# power_supply.net
KiCad netlist of a schematic drawn in Altium Designer
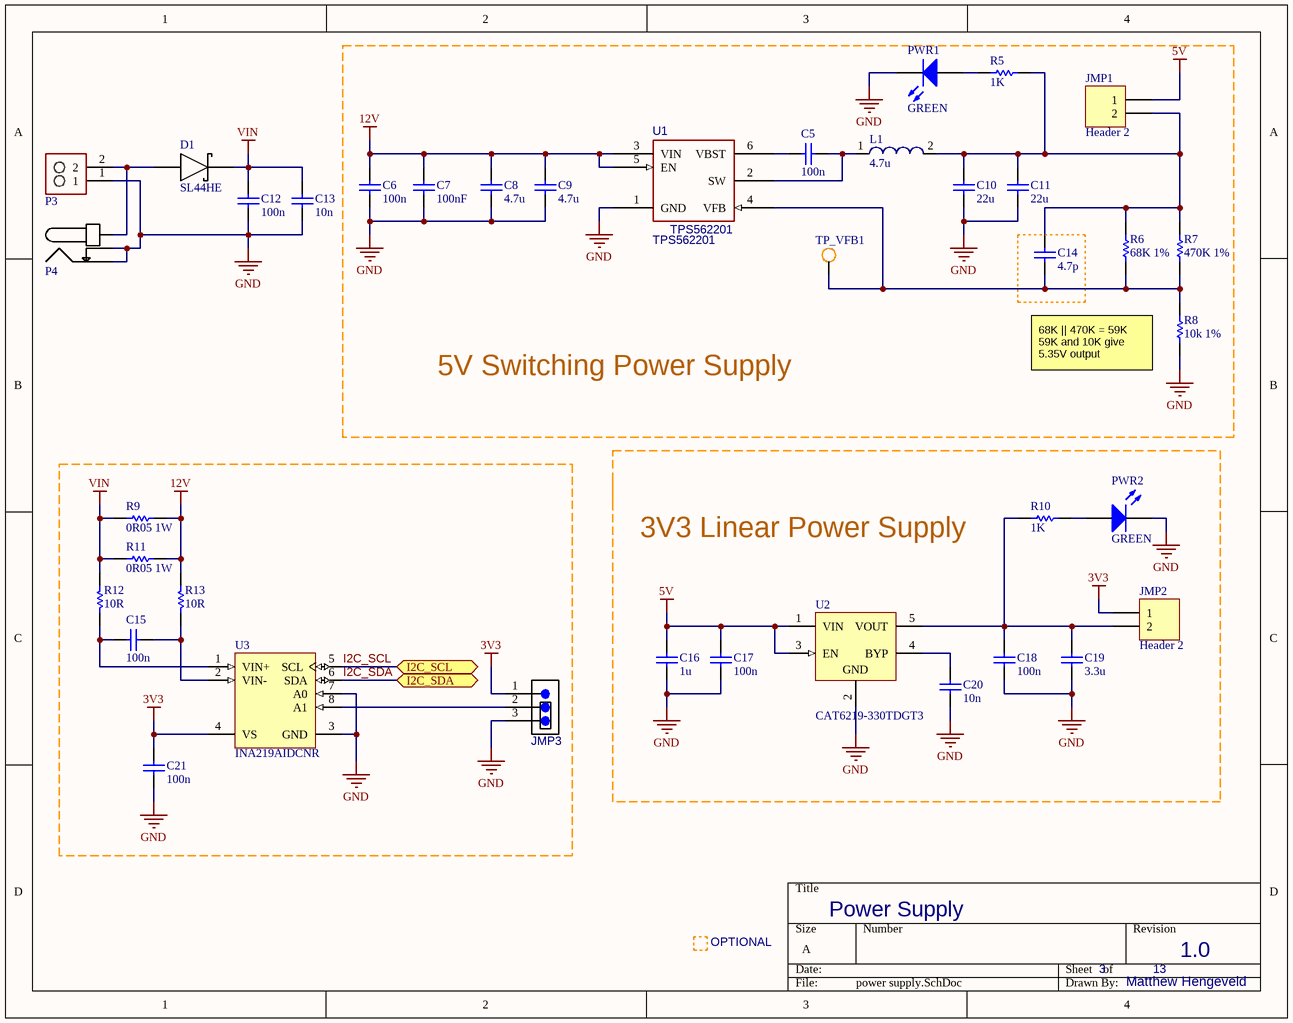
[diagram p0: power supply.SchDoc]

(export (version "E")
  (design (tool "Eeschema 10.0.6"))
  (components
    (comp (ref "C5")
      (value "100n")
      (footprint "CAPC2113X100X50LL30T25")
      (fields (field (name "MANUFACTURER") "Kemet") (field (name "PART NUMBER") "C0805X104K5RACTU"))
      (libsource (lib "Altium Content Vault") (part "CAP"))
    )
    (comp (ref "C6")
      (value "100n")
      (footprint "CAPC1608X90X35LL15T15")
      (description "Chip Capacitor, 100 nF, +/- 10%, 50 V, -55 to 125 degC, 0603 (1608 Metric), RoHS, Tape and Reel")
      (fields (field (name "TOLERANCE") "10%"))
      (libsource (lib "Altium Content Vault") (part "CAP-NP-2"))
    )
    (comp (ref "C7")
      (value "100nF")
      (footprint "CAPC2013X94X50LL20T25")
      (fields
        (field (name "PART NUMBER") "08055C104K4T2A")
        (field (name "MANUFACTURER") "AVX Interconnect / Elco")
      )
      (libsource (lib "Altium Content Vault") (part "CAP"))
    )
    (comp (ref "C8")
      (value "4.7u")
      (footprint "CAPC3225X220X20ML40")
      (description "Chip Capacitor, 4.7 uF, +/- 20%, 100 V, -55 to 125 degC, 1210 (3225 Metric), RoHS, Tape and Reel")
      (fields
        (field (name "PCN PART NUMBER") "MLCCPartNumberChange30/Nov/2012")
        (field (name "MANUFACTURER") "TDK")
      )
      (libsource (lib "Altium Content Vault") (part "CAP-NP-2"))
    )
    (comp (ref "C9")
      (value "4.7u")
      (footprint "CAPC3225X220X20ML40")
      (description "Chip Capacitor, 4.7 uF, +/- 20%, 100 V, -55 to 125 degC, 1210 (3225 Metric), RoHS, Tape and Reel")
      (fields
        (field (name "PCN PART NUMBER") "MLCCPartNumberChange30/Nov/2012")
        (field (name "MANUFACTURER") "TDK")
      )
      (libsource (lib "Altium Content Vault") (part "CAP-NP-2"))
    )
    (comp (ref "C10")
      (value "22u")
      (footprint "CAPC3225X220X20ML40")
      (description "Chip Capacitor, 4.7 uF, +/- 20%, 100 V, -55 to 125 degC, 1210 (3225 Metric), RoHS, Tape and Reel")
      (fields
        (field (name "PCN PART NUMBER") "MLCCPartNumberChange30/Nov/2012")
        (field (name "MANUFACTURER") "TDK")
      )
      (libsource (lib "Altium Content Vault") (part "CAP-NP-2"))
    )
    (comp (ref "C11")
      (value "22u")
      (footprint "CAPC3225X220X20ML40")
      (description "Chip Capacitor, 4.7 uF, +/- 20%, 100 V, -55 to 125 degC, 1210 (3225 Metric), RoHS, Tape and Reel")
      (fields
        (field (name "PCN PART NUMBER") "MLCCPartNumberChange30/Nov/2012")
        (field (name "MANUFACTURER") "TDK")
      )
      (libsource (lib "Altium Content Vault") (part "CAP-NP-2"))
    )
    (comp (ref "C12")
      (value "100n")
      (footprint "CAPC2013X95X45LL15T25")
      (fields (field (name "PART NUMBER") "GCM2195C1H103JA16D") (field (name "MANUFACTURER") "Murata"))
      (libsource (lib "Altium Content Vault") (part "CAP"))
    )
    (comp (ref "C13")
      (value "10n")
      (footprint "CAPC2013X95X45LL15T25")
      (fields (field (name "PART NUMBER") "GCM2195C1H103JA16D") (field (name "MANUFACTURER") "Murata"))
      (libsource (lib "Altium Content Vault") (part "CAP"))
    )
    (comp (ref "C14")
      (value "4.7p")
      (footprint "CAPC1608X87X35LL15T15")
      (fields (field (name "MANUFACTURER") "Kemet") (field (name "PART NUMBER") "C0603C104K3RACTU"))
      (libsource (lib "Altium Content Vault") (part "CAP"))
    )
    (comp (ref "C15")
      (value "100n")
      (footprint "CAPC1608X87X35LL15T15")
      (fields (field (name "PART NUMBER") "C0603X104K5RACTU") (field (name "MANUFACTURER") "Kemet"))
      (libsource (lib "Altium Content Vault") (part "CAP"))
    )
    (comp (ref "C16")
      (value "1u")
      (footprint "CAPC2013X140X50LL20T25")
      (fields
        (field (name "PART NUMBER") "0805ZC105KAT2A")
        (field (name "MANUFACTURER") "AVX Interconnect / Elco")
      )
      (libsource (lib "Altium Content Vault") (part "CAP"))
    )
    (comp (ref "C17")
      (value "100n")
      (footprint "CAPC1608X87X35LL15T15")
      (fields (field (name "MANUFACTURER") "Kemet") (field (name "PART NUMBER") "C0603C104K3RACTU"))
      (libsource (lib "Altium Content Vault") (part "CAP"))
    )
    (comp (ref "C18")
      (value "100n")
      (footprint "CAPC1608X87X35LL15T15")
      (fields (field (name "MANUFACTURER") "Kemet") (field (name "PART NUMBER") "C0603C104K3RACTU"))
      (libsource (lib "Altium Content Vault") (part "CAP"))
    )
    (comp (ref "C19")
      (value "3.3u")
      (footprint "CAPC3225X220X20ML40")
      (description "Chip Capacitor, 4.7 uF, +/- 20%, 100 V, -55 to 125 degC, 1210 (3225 Metric), RoHS, Tape and Reel")
      (fields
        (field (name "PCN PART NUMBER") "MLCCPartNumberChange30/Nov/2012")
        (field (name "MANUFACTURER") "TDK")
      )
      (libsource (lib "Altium Content Vault") (part "CAP-NP-2"))
    )
    (comp (ref "C20")
      (value "10n")
      (footprint "CAPC1608X87X35LL15T15")
      (fields (field (name "MANUFACTURER") "Kemet") (field (name "PART NUMBER") "C0603C104K3RACTU"))
      (libsource (lib "Altium Content Vault") (part "CAP"))
    )
    (comp (ref "C21")
      (value "100n")
      (footprint "CAPC1608X87X35LL15T15")
      (fields (field (name "PART NUMBER") "C0603X104K5RACTU") (field (name "MANUFACTURER") "Kemet"))
      (libsource (lib "Altium Content Vault") (part "CAP"))
    )
    (comp (ref "D1")
      (value "SL44HE")
      (footprint "SMC Diode")
      (description "Schottky Power Rectifier, 2-Pin SMC, 40V, 8A")
      (fields (field (name "PARTNUMBER") "MBRS540T3") (field (name "MANUFACTURER") "On Semiconductor"))
      (libsource (lib "Hengeveld") (part "SL44HE"))
    )
    (comp (ref "JMP1")
      (value "Header 2")
      (footprint "HDR1X2")
      (description "Header, 2-Pin")
      (fields (field (name "PUBLISHER") "Altium Limited"))
      (libsource (lib "") (part "Header 2_1"))
    )
    (comp (ref "JMP2")
      (value "Header 2")
      (footprint "HDR1X2")
      (description "Header, 2-Pin")
      (fields (field (name "PUBLISHER") "Altium Limited"))
      (libsource (lib "Hengeveld") (part "Header 2"))
    )
    (comp (ref "JMP3")
      (value "SMD_JMP")
      (footprint "0603_JUMPER")
      (libsource (lib "Hengeveld") (part "SMD_JMP"))
    )
    (comp (ref "L1")
      (value "4.7u")
      (footprint "WE-LQS 6045")
      (description "WE-LQS SMD Power Inductor, L=4.7 µH")
      (fields (field (name "MANUFACTURER") "Wuerth Elektronik") (field (name "PARTNUMBER") "74404064047"))
      (libsource (lib "Altium Content Vault") (part "WE-IND-INDUCTOR-2"))
    )
    (comp (ref "P3")
      (value "2PIN_SCREW_TERM_3_5MM")
      (footprint "2PIN_SCREWW_TERM_3_5MM")
      (libsource (lib "Hengeveld") (part "2PIN_SCREW_TERM_3_5MM"))
    )
    (comp (ref "P4")
      (value "Barrel Jack")
      (footprint "2.1x5.5mm Barrel Jack - Holes")
      (libsource (lib "Hengeveld") (part "Barrel Jack"))
    )
    (comp (ref "PWR1")
      (value "GREEN")
      (footprint "0805_A")
      (description "SMD mono-color Chip LED, WL-SMCW, Red")
      (fields (field (name "PARTNUMBER") "150080RS75000") (field (name "MANUFACTURER") "Wuerth Elektronik"))
      (libsource (lib "Altium Content Vault") (part "WE-LED_K1A2-2"))
    )
    (comp (ref "PWR2")
      (value "GREEN")
      (footprint "0805_A")
      (description "SMD mono-color Chip LED, WL-SMCW, Red")
      (fields (field (name "PARTNUMBER") "150080RS75000") (field (name "MANUFACTURER") "Wuerth Elektronik"))
      (libsource (lib "Altium Content Vault") (part "WE-LED_K1A2-2"))
    )
    (comp (ref "R5")
      (value "1K")
      (footprint "RESC1608X55X30LL15T15")
      (fields (field (name "PART NUMBER") "ERJ-3EKF1002V") (field (name "MANUFACTURER") "Panasonic"))
      (libsource (lib "Altium Content Vault") (part "RES"))
    )
    (comp (ref "R6")
      (value "68K 1%")
      (footprint "RESC1608X55X30LL15T15")
      (fields (field (name "PART NUMBER") "ERJ-3EKF1002V") (field (name "MANUFACTURER") "Panasonic"))
      (libsource (lib "Altium Content Vault") (part "RES"))
    )
    (comp (ref "R7")
      (value "470K 1%")
      (footprint "RESC1608X55X30LL15T15")
      (fields (field (name "PART NUMBER") "ERJ-3EKF1002V") (field (name "MANUFACTURER") "Panasonic"))
      (libsource (lib "Altium Content Vault") (part "RES"))
    )
    (comp (ref "R8")
      (value "10k 1%")
      (footprint "RESC1608X55X30LL15T15")
      (fields (field (name "PART NUMBER") "ERJ-3EKF1002V") (field (name "MANUFACTURER") "Panasonic"))
      (libsource (lib "Altium Content Vault") (part "RES"))
    )
    (comp (ref "R9")
      (value "0R05 1W")
      (footprint "ROHM-MCR100-2_V")
      (fields
        (field (name "PARTNUMBER") "MCR100JZHFLR470")
        (field (name "MANUFACTURER") "ROHM Semiconductor")
      )
      (libsource (lib "Altium Content Vault") (part "ROHM-RES-2"))
    )
    (comp (ref "R10")
      (value "1K")
      (footprint "RESC1608X55X30LL15T15")
      (fields (field (name "PART NUMBER") "ERJ-3EKF1002V") (field (name "MANUFACTURER") "Panasonic"))
      (libsource (lib "Altium Content Vault") (part "RES"))
    )
    (comp (ref "R11")
      (value "0R05 1W")
      (footprint "ROHM-MCR100-2_V")
      (fields
        (field (name "PARTNUMBER") "MCR100JZHFLR470")
        (field (name "MANUFACTURER") "ROHM Semiconductor")
      )
      (libsource (lib "Altium Content Vault") (part "ROHM-RES-2"))
    )
    (comp (ref "R12")
      (value "10R")
      (footprint "RESC1608X55X30LL15T15")
      (fields (field (name "MANUFACTURER") "Panasonic") (field (name "PART NUMBER") "ERJ-3GEYJ103V"))
      (libsource (lib "Altium Content Vault") (part "RES"))
    )
    (comp (ref "R13")
      (value "10R")
      (footprint "RESC1608X55X30LL15T15")
      (fields (field (name "MANUFACTURER") "Panasonic") (field (name "PART NUMBER") "ERJ-3GEYJ103V"))
      (libsource (lib "Altium Content Vault") (part "RES"))
    )
    (comp (ref "TP_VFB1")
      (value "Test point")
      (footprint "SMD Test Hook")
      (libsource (lib "Hengeveld") (part "Test Point"))
    )
    (comp (ref "U1")
      (value "TPS562201")
      (footprint "MCHP-SOT-23-OT6_N")
      (libsource (lib "Hengeveld") (part "TPS562201"))
    )
    (comp (ref "U2")
      (value "CAT6219-330TDGT3")
      (footprint "SOT-23-5")
      (description "Fixed Low Drop Positive Voltage Regulator, 3.3V, 5-Pin TSOT-23, Tape and Reel")
      (fields (field (name "MANUFACTURER") "ON Semiconductor"))
      (libsource (lib "Hengeveld") (part "CAT6219"))
    )
    (comp (ref "U3")
      (value "INA219AIDCNR")
      (footprint "SOT-23-8")
      (fields (field (name "MANUFACTURER") "Texas Instruments"))
      (libsource (lib "Hengeveld") (part "INA219"))
    )
  )
  (nets
    (net (code "1") (name "/I2C_SCL") (class "Default")
      (node (ref "U3") (pin "5") (pinfunction "SCL_5") (pintype "bidirectional"))
    )
    (net (code "2") (name "/I2C_SDA") (class "Default")
      (node (ref "U3") (pin "6") (pinfunction "SDA_6") (pintype "bidirectional"))
    )
    (net (code "3") (name "3V3") (class "Default")
      (node (ref "C21") (pin "2") (pinfunction "2_2") (pintype "passive"))
      (node (ref "JMP2") (pin "1") (pinfunction "1_1") (pintype "passive"))
      (node (ref "JMP3") (pin "1") (pinfunction "1_1") (pintype "passive"))
      (node (ref "U3") (pin "4") (pinfunction "VS_4") (pintype "power_in"))
    )
    (net (code "4") (name "5V") (class "Default")
      (node (ref "C16") (pin "2") (pinfunction "2_2") (pintype "passive"))
      (node (ref "C17") (pin "2") (pinfunction "2_2") (pintype "passive"))
      (node (ref "JMP1") (pin "1") (pinfunction "1_1") (pintype "passive"))
      (node (ref "U2") (pin "1") (pinfunction "VIN_1") (pintype "power_in"))
      (node (ref "U2") (pin "3") (pinfunction "EN_3") (pintype "input"))
    )
    (net (code "5") (name "12V") (class "Default")
      (node (ref "C6") (pin "2") (pinfunction "2_2") (pintype "passive"))
      (node (ref "C7") (pin "1") (pinfunction "1_1") (pintype "passive"))
      (node (ref "C8") (pin "2") (pinfunction "2_2") (pintype "passive"))
      (node (ref "C9") (pin "2") (pinfunction "2_2") (pintype "passive"))
      (node (ref "R11") (pin "2") (pinfunction "2_2") (pintype "passive"))
      (node (ref "R13") (pin "1") (pinfunction "1_1") (pintype "passive"))
      (node (ref "R9") (pin "2") (pinfunction "2_2") (pintype "passive"))
      (node (ref "U1") (pin "3") (pinfunction "VIN_3") (pintype "power_in"))
      (node (ref "U1") (pin "5") (pinfunction "EN_5") (pintype "input"))
    )
    (net (code "6") (name "GND") (class "Default")
      (node (ref "C10") (pin "1") (pinfunction "1_1") (pintype "passive"))
      (node (ref "C11") (pin "1") (pinfunction "1_1") (pintype "passive"))
      (node (ref "C12") (pin "1") (pinfunction "1_1") (pintype "passive"))
      (node (ref "C13") (pin "1") (pinfunction "1_1") (pintype "passive"))
      (node (ref "C16") (pin "1") (pinfunction "1_1") (pintype "passive"))
      (node (ref "C17") (pin "1") (pinfunction "1_1") (pintype "passive"))
      (node (ref "C18") (pin "1") (pinfunction "1_1") (pintype "passive"))
      (node (ref "C19") (pin "1") (pinfunction "1_1") (pintype "passive"))
      (node (ref "C20") (pin "1") (pinfunction "1_1") (pintype "passive"))
      (node (ref "C21") (pin "1") (pinfunction "1_1") (pintype "passive"))
      (node (ref "C6") (pin "1") (pinfunction "1_1") (pintype "passive"))
      (node (ref "C7") (pin "2") (pinfunction "2_2") (pintype "passive"))
      (node (ref "C8") (pin "1") (pinfunction "1_1") (pintype "passive"))
      (node (ref "C9") (pin "1") (pinfunction "1_1") (pintype "passive"))
      (node (ref "JMP3") (pin "3") (pinfunction "3_3") (pintype "passive"))
      (node (ref "P3") (pin "1") (pinfunction "1_1") (pintype "passive"))
      (node (ref "P4") (pin "2") (pinfunction "2_2") (pintype "passive"))
      (node (ref "P4") (pin "3") (pinfunction "3_3") (pintype "passive"))
      (node (ref "PWR1") (pin "1") (pinfunction "K_1") (pintype "passive"))
      (node (ref "PWR2") (pin "1") (pinfunction "K_1") (pintype "passive"))
      (node (ref "R8") (pin "1") (pinfunction "1_1") (pintype "passive"))
      (node (ref "U1") (pin "1") (pinfunction "GND_1") (pintype "power_in"))
      (node (ref "U2") (pin "2") (pinfunction "GND_2") (pintype "power_in"))
      (node (ref "U3") (pin "3") (pinfunction "GND_3") (pintype "power_in"))
      (node (ref "U3") (pin "7") (pinfunction "A0_7") (pintype "input"))
    )
    (net (code "7") (name "Net-(C10-Pad2)") (class "Default")
      (node (ref "C10") (pin "2") (pinfunction "2_2") (pintype "passive"))
      (node (ref "C11") (pin "2") (pinfunction "2_2") (pintype "passive"))
      (node (ref "C14") (pin "2") (pinfunction "2_2") (pintype "passive"))
      (node (ref "JMP1") (pin "2") (pinfunction "2_2") (pintype "passive"))
      (node (ref "L1") (pin "2") (pinfunction "2_2") (pintype "passive"))
      (node (ref "R5") (pin "1") (pinfunction "1_1") (pintype "passive"))
      (node (ref "R6") (pin "2") (pinfunction "2_2") (pintype "passive"))
      (node (ref "R7") (pin "2") (pinfunction "2_2") (pintype "passive"))
    )
    (net (code "8") (name "Net-(D1-A)") (class "Default")
      (node (ref "D1") (pin "2") (pinfunction "A_2") (pintype "passive"))
      (node (ref "P3") (pin "2") (pinfunction "2_2") (pintype "passive"))
      (node (ref "P4") (pin "1") (pinfunction "1_1") (pintype "passive"))
    )
    (net (code "9") (name "Net-(PWR1-A)") (class "Default")
      (node (ref "PWR1") (pin "2") (pinfunction "A_2") (pintype "passive"))
      (node (ref "R5") (pin "2") (pinfunction "2_2") (pintype "passive"))
    )
    (net (code "10") (name "Net-(PWR2-A)") (class "Default")
      (node (ref "PWR2") (pin "2") (pinfunction "A_2") (pintype "passive"))
      (node (ref "R10") (pin "1") (pinfunction "1_1") (pintype "passive"))
    )
    (net (code "11") (name "Net-(TP_VFB1-point)") (class "Default")
      (node (ref "C14") (pin "1") (pinfunction "1_1") (pintype "passive"))
      (node (ref "R6") (pin "1") (pinfunction "1_1") (pintype "passive"))
      (node (ref "R7") (pin "1") (pinfunction "1_1") (pintype "passive"))
      (node (ref "R8") (pin "2") (pinfunction "2_2") (pintype "passive"))
      (node (ref "TP_VFB1") (pin "1") (pinfunction "point_1") (pintype "passive"))
      (node (ref "U1") (pin "4") (pinfunction "VFB_4") (pintype "input"))
    )
    (net (code "12") (name "Net-(U1-SW)") (class "Default")
      (node (ref "C5") (pin "2") (pinfunction "2_2") (pintype "passive"))
      (node (ref "L1") (pin "1") (pinfunction "1_1") (pintype "passive"))
      (node (ref "U1") (pin "2") (pinfunction "SW_2") (pintype "power_in"))
    )
    (net (code "13") (name "Net-(U1-VBST)") (class "Default")
      (node (ref "C5") (pin "1") (pinfunction "1_1") (pintype "passive"))
      (node (ref "U1") (pin "6") (pinfunction "VBST_6") (pintype "power_in"))
    )
    (net (code "14") (name "Net-(U2-BYP)") (class "Default")
      (node (ref "C20") (pin "2") (pinfunction "2_2") (pintype "passive"))
      (node (ref "U2") (pin "4") (pinfunction "BYP_4") (pintype "passive"))
    )
    (net (code "15") (name "Net-(U2-VOUT)") (class "Default")
      (node (ref "C18") (pin "2") (pinfunction "2_2") (pintype "passive"))
      (node (ref "C19") (pin "2") (pinfunction "2_2") (pintype "passive"))
      (node (ref "JMP2") (pin "2") (pinfunction "2_2") (pintype "passive"))
      (node (ref "R10") (pin "2") (pinfunction "2_2") (pintype "passive"))
      (node (ref "U2") (pin "5") (pinfunction "VOUT_5") (pintype "power_in"))
    )
    (net (code "16") (name "Net-(U3-A1)") (class "Default")
      (node (ref "JMP3") (pin "2") (pinfunction "2_2") (pintype "passive"))
      (node (ref "U3") (pin "8") (pinfunction "A1_8") (pintype "input"))
    )
    (net (code "17") (name "Net-(U3-VIN+)") (class "Default")
      (node (ref "C15") (pin "1") (pinfunction "1_1") (pintype "passive"))
      (node (ref "R12") (pin "2") (pinfunction "2_2") (pintype "passive"))
      (node (ref "U3") (pin "1") (pinfunction "VIN+_1") (pintype "input"))
    )
    (net (code "18") (name "Net-(U3-VIN-)") (class "Default")
      (node (ref "C15") (pin "2") (pinfunction "2_2") (pintype "passive"))
      (node (ref "R13") (pin "2") (pinfunction "2_2") (pintype "passive"))
      (node (ref "U3") (pin "2") (pinfunction "VIN-_2") (pintype "input"))
    )
    (net (code "19") (name "VIN") (class "Default")
      (node (ref "C12") (pin "2") (pinfunction "2_2") (pintype "passive"))
      (node (ref "C13") (pin "2") (pinfunction "2_2") (pintype "passive"))
      (node (ref "D1") (pin "1") (pinfunction "K_1") (pintype "passive"))
      (node (ref "R11") (pin "1") (pinfunction "1_1") (pintype "passive"))
      (node (ref "R12") (pin "1") (pinfunction "1_1") (pintype "passive"))
      (node (ref "R9") (pin "1") (pinfunction "1_1") (pintype "passive"))
    )
  )
)
